# clap_switch_smd.net
KiCad netlist of a schematic drawn in EAGLE
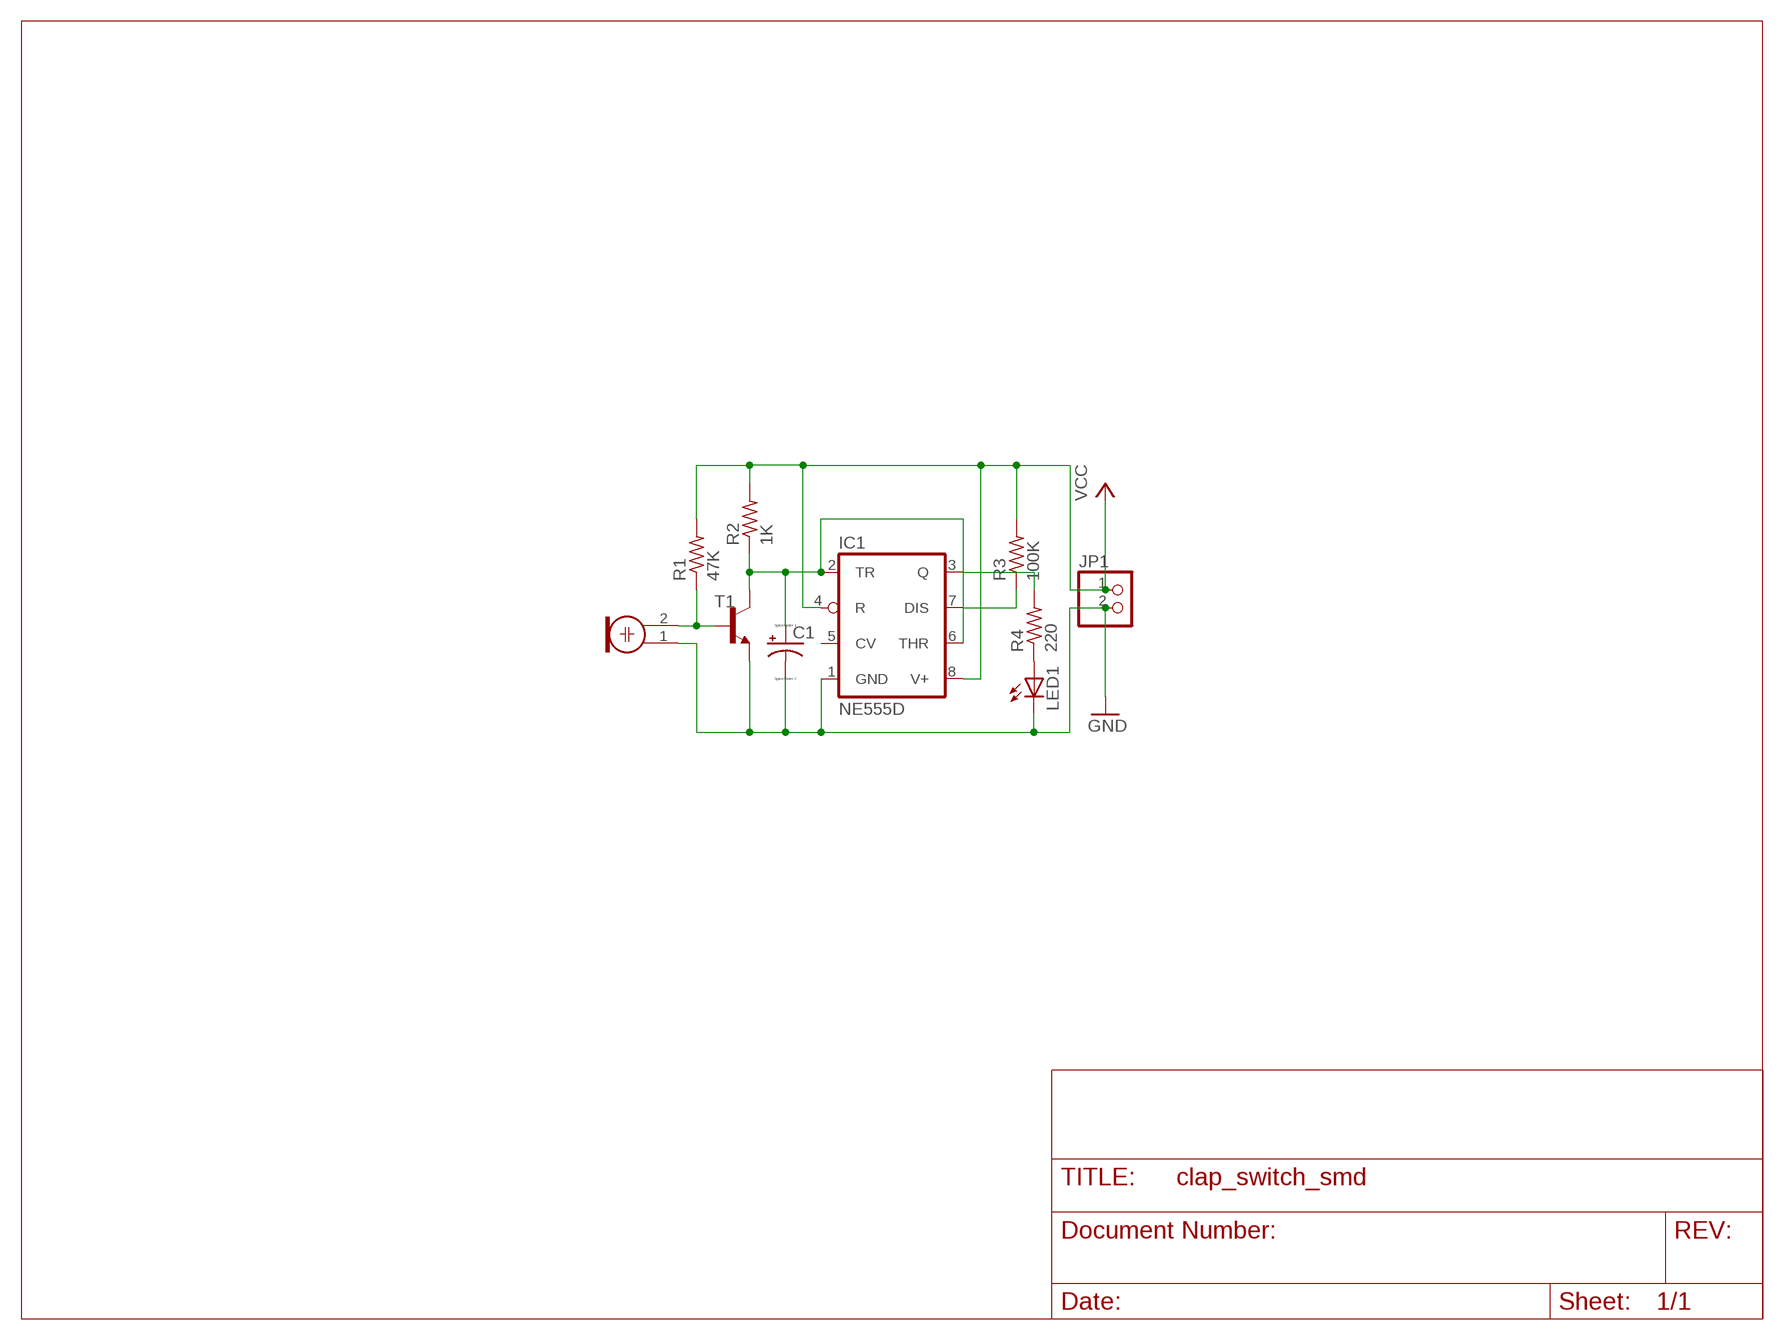
[diagram p0: schematic, sheet 1]

(export (version "E")
  (design (tool "Eeschema 10.0.6"))
  (components
    (comp (ref "C1")
      (value "CPOL-US153CLV-0405")
      (footprint "eagle-import:153CLV-0405")
      (libsource (lib "eagle-import") (part "CPOL-US153CLV-0405"))
    )
    (comp (ref "IC1")
      (value "NE555D")
      (footprint "eagle-import:SO08")
      (libsource (lib "eagle-import") (part "555DNE"))
    )
    (comp (ref "JP1")
      (value "PINHD-1X2")
      (footprint "eagle-import:1X02")
      (libsource (lib "eagle-import") (part "PINHD-1X2"))
    )
    (comp (ref "LED1")
      (value "LEDCHIP-LED0603")
      (footprint "eagle-import:CHIP-LED0603")
      (libsource (lib "eagle-import") (part "LEDCHIP-LED0603"))
    )
    (comp (ref "M1")
      (value "MIC")
      (footprint "eagle-import:WM-61A")
      (libsource (lib "eagle-import") (part "ELECTRET_MICROPHON-WM-61A"))
    )
    (comp (ref "R1")
      (value "47K")
      (footprint "eagle-import:R0603")
      (libsource (lib "eagle-import") (part "R-US_R0603"))
    )
    (comp (ref "R2")
      (value "1K")
      (footprint "eagle-import:R0603")
      (libsource (lib "eagle-import") (part "R-US_R0603"))
    )
    (comp (ref "R3")
      (value "100K")
      (footprint "eagle-import:R0603")
      (libsource (lib "eagle-import") (part "R-US_R0603"))
    )
    (comp (ref "R4")
      (value "220")
      (footprint "eagle-import:R0603")
      (libsource (lib "eagle-import") (part "R-US_R0603"))
    )
    (comp (ref "T1")
      (value "MMBT3904LT1-NPN-SOT23-BEC")
      (footprint "eagle-import:SOT23-BEC")
      (libsource (lib "eagle-import") (part "-NPN-SOT23-BECMMBT3904LT1"))
    )
  )
  (nets
    (net (code "1") (name "GND") (class "Default")
      (node (ref "C1") (pin "-") (pinfunction "-_-") (pintype "passive"))
      (node (ref "IC1") (pin "1") (pinfunction "GND_1") (pintype "power_in"))
      (node (ref "JP1") (pin "2") (pinfunction "2_2") (pintype "passive"))
      (node (ref "LED1") (pin "C") (pinfunction "C_C") (pintype "passive"))
      (node (ref "M1") (pin "1") (pinfunction "1_1") (pintype "passive"))
      (node (ref "T1") (pin "E") (pinfunction "E_E") (pintype "passive"))
    )
    (net (code "2") (name "Net-(IC1-DIS)") (class "Default")
      (node (ref "IC1") (pin "7") (pinfunction "DIS_7") (pintype "input"))
      (node (ref "R3") (pin "1") (pinfunction "1_1") (pintype "passive"))
    )
    (net (code "3") (name "Net-(IC1-Q)") (class "Default")
      (node (ref "IC1") (pin "3") (pinfunction "Q_3") (pintype "output"))
      (node (ref "R4") (pin "2") (pinfunction "2_2") (pintype "passive"))
    )
    (net (code "4") (name "Net-(IC1-THR)") (class "Default")
      (node (ref "C1") (pin "+") (pinfunction "+_+") (pintype "passive"))
      (node (ref "IC1") (pin "2") (pinfunction "TR_2") (pintype "input"))
      (node (ref "IC1") (pin "6") (pinfunction "THR_6") (pintype "input"))
      (node (ref "R2") (pin "1") (pinfunction "1_1") (pintype "passive"))
      (node (ref "T1") (pin "C") (pinfunction "C_C") (pintype "passive"))
    )
    (net (code "5") (name "Net-(LED1-PadA)") (class "Default")
      (node (ref "LED1") (pin "A") (pinfunction "A_A") (pintype "passive"))
      (node (ref "R4") (pin "1") (pinfunction "1_1") (pintype "passive"))
    )
    (net (code "6") (name "Net-(M1-Pad2)") (class "Default")
      (node (ref "M1") (pin "2") (pinfunction "2_2") (pintype "passive"))
      (node (ref "R1") (pin "1") (pinfunction "1_1") (pintype "passive"))
      (node (ref "T1") (pin "B") (pinfunction "B_B") (pintype "passive"))
    )
    (net (code "7") (name "VCC") (class "Default")
      (node (ref "IC1") (pin "4") (pinfunction "R_4") (pintype "input"))
      (node (ref "IC1") (pin "8") (pinfunction "V+_8") (pintype "power_in"))
      (node (ref "JP1") (pin "1") (pinfunction "1_1") (pintype "passive"))
      (node (ref "R1") (pin "2") (pinfunction "2_2") (pintype "passive"))
      (node (ref "R2") (pin "2") (pinfunction "2_2") (pintype "passive"))
      (node (ref "R3") (pin "2") (pinfunction "2_2") (pintype "passive"))
    )
    (net (code "8") (name "unconnected-(IC1-CV-Pad5)") (class "Default")
      (node (ref "IC1") (pin "5") (pinfunction "CV_5") (pintype "input"))
    )
  )
)
